# P6_CCD_CAM_BOARD_HDMI.net
KiCad netlist of a schematic drawn in Altium Designer
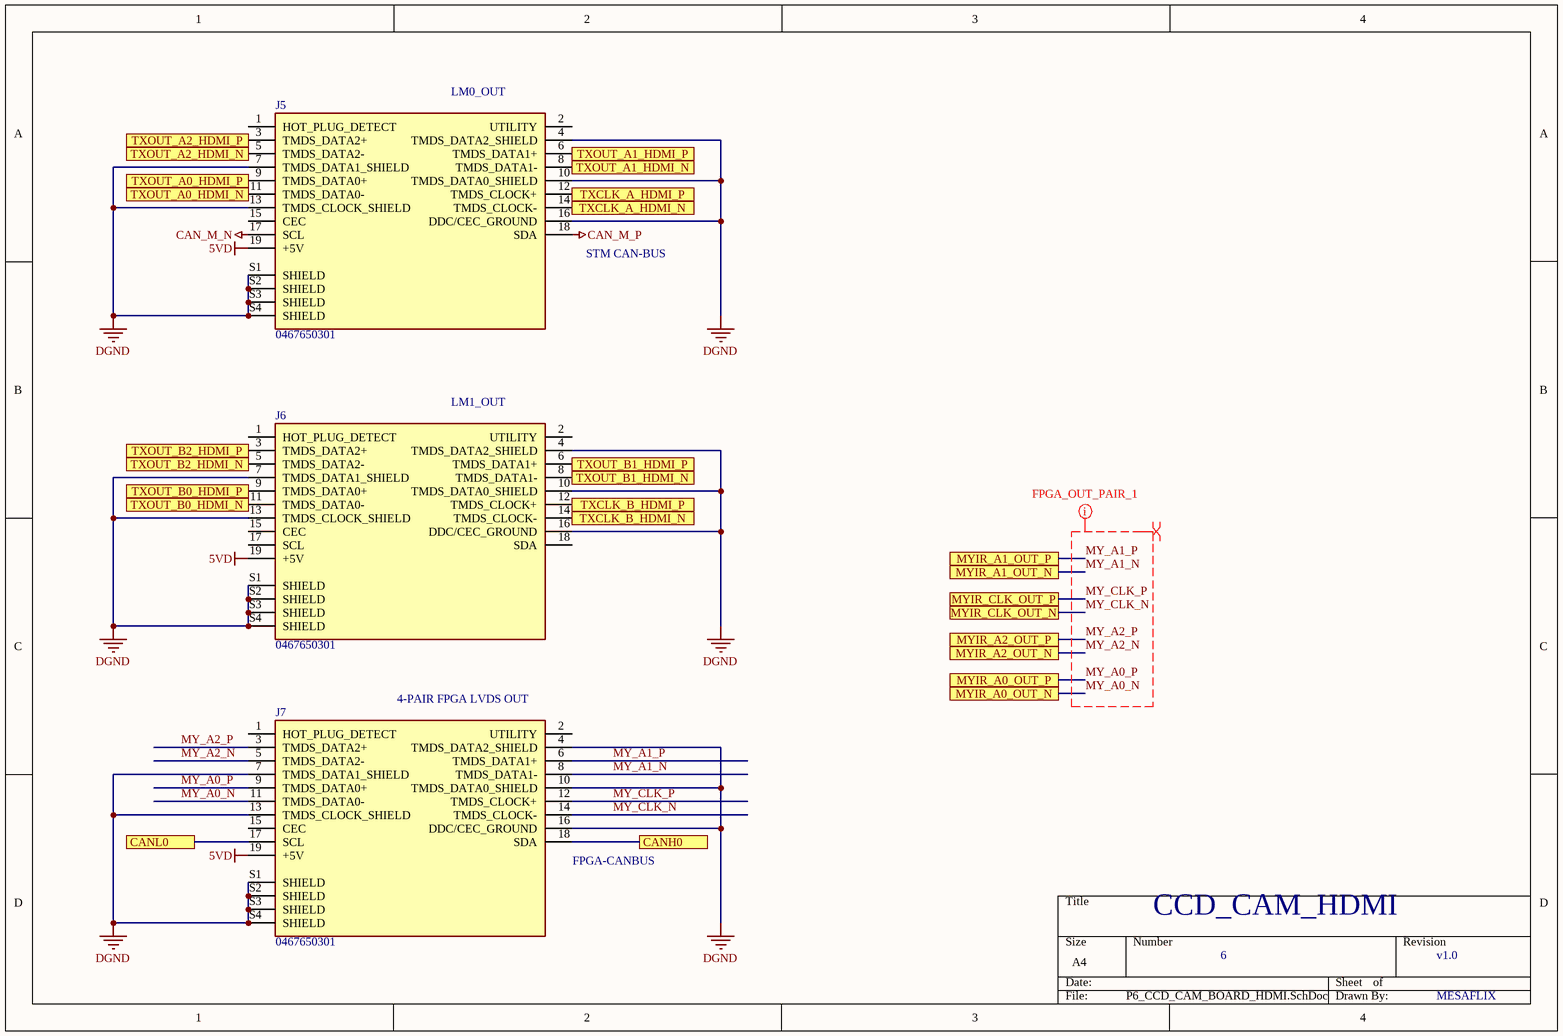
[diagram p0: P6_CCD_CAM_BOARD_HDMI.SchDoc]

(export (version "E")
  (design (tool "Eeschema 10.0.6"))
  (components
    (comp (ref "J5")
      (value "0467650301")
      (footprint "MOLEX_0467650301")
      (description "HDMI - Micro Receptacle Connector 19 Position Surface Mount, Right Angle")
      (fields (field (name "MF") "Molex"))
      (libsource (lib "CCD_CAM_BOARD_1") (part "0467650301"))
    )
    (comp (ref "J6")
      (value "0467650301")
      (footprint "MOLEX_0467650301")
      (description "HDMI - Micro Receptacle Connector 19 Position Surface Mount, Right Angle")
      (fields (field (name "MF") "Molex"))
      (libsource (lib "CCD_CAM_BOARD_1") (part "0467650301"))
    )
    (comp (ref "J7")
      (value "0467650301")
      (footprint "MOLEX_0467650301")
      (description "HDMI - Micro Receptacle Connector 19 Position Surface Mount, Right Angle")
      (fields (field (name "MF") "Molex"))
      (libsource (lib "CCD_CAM_BOARD_1") (part "0467650301"))
    )
  )
  (nets
    (net (code "1") (name "/CANH0") (class "Default")
      (node (ref "J7") (pin "18") (pinfunction "SDA_18") (pintype "passive"))
    )
    (net (code "2") (name "/CANL0") (class "Default")
      (node (ref "J7") (pin "17") (pinfunction "SCL_17") (pintype "passive"))
    )
    (net (code "3") (name "/MY_A0_N") (class "Default")
      (node (ref "J7") (pin "11") (pinfunction "TMDS_DATA0-_11") (pintype "passive"))
    )
    (net (code "4") (name "/MY_A0_P") (class "Default")
      (node (ref "J7") (pin "9") (pinfunction "TMDS_DATA0+_9") (pintype "passive"))
    )
    (net (code "5") (name "/MY_A1_N") (class "Default")
      (node (ref "J7") (pin "8") (pinfunction "TMDS_DATA1-_8") (pintype "passive"))
    )
    (net (code "6") (name "/MY_A1_P") (class "Default")
      (node (ref "J7") (pin "6") (pinfunction "TMDS_DATA1+_6") (pintype "passive"))
    )
    (net (code "7") (name "/MY_A2_N") (class "Default")
      (node (ref "J7") (pin "5") (pinfunction "TMDS_DATA2-_5") (pintype "passive"))
    )
    (net (code "8") (name "/MY_A2_P") (class "Default")
      (node (ref "J7") (pin "3") (pinfunction "TMDS_DATA2+_3") (pintype "passive"))
    )
    (net (code "9") (name "/MY_CLK_N") (class "Default")
      (node (ref "J7") (pin "14") (pinfunction "TMDS_CLOCK-_14") (pintype "passive"))
    )
    (net (code "10") (name "/MY_CLK_P") (class "Default")
      (node (ref "J7") (pin "12") (pinfunction "TMDS_CLOCK+_12") (pintype "passive"))
    )
    (net (code "11") (name "/TXCLK_A_HDMI_N") (class "Default")
      (node (ref "J5") (pin "14") (pinfunction "TMDS_CLOCK-_14") (pintype "passive"))
    )
    (net (code "12") (name "/TXCLK_A_HDMI_P") (class "Default")
      (node (ref "J5") (pin "12") (pinfunction "TMDS_CLOCK+_12") (pintype "passive"))
    )
    (net (code "13") (name "/TXCLK_B_HDMI_N") (class "Default")
      (node (ref "J6") (pin "14") (pinfunction "TMDS_CLOCK-_14") (pintype "passive"))
    )
    (net (code "14") (name "/TXCLK_B_HDMI_P") (class "Default")
      (node (ref "J6") (pin "12") (pinfunction "TMDS_CLOCK+_12") (pintype "passive"))
    )
    (net (code "15") (name "/TXOUT_A0_HDMI_N") (class "Default")
      (node (ref "J5") (pin "11") (pinfunction "TMDS_DATA0-_11") (pintype "passive"))
    )
    (net (code "16") (name "/TXOUT_A0_HDMI_P") (class "Default")
      (node (ref "J5") (pin "9") (pinfunction "TMDS_DATA0+_9") (pintype "passive"))
    )
    (net (code "17") (name "/TXOUT_A1_HDMI_N") (class "Default")
      (node (ref "J5") (pin "8") (pinfunction "TMDS_DATA1-_8") (pintype "passive"))
    )
    (net (code "18") (name "/TXOUT_A1_HDMI_P") (class "Default")
      (node (ref "J5") (pin "6") (pinfunction "TMDS_DATA1+_6") (pintype "passive"))
    )
    (net (code "19") (name "/TXOUT_A2_HDMI_N") (class "Default")
      (node (ref "J5") (pin "5") (pinfunction "TMDS_DATA2-_5") (pintype "passive"))
    )
    (net (code "20") (name "/TXOUT_A2_HDMI_P") (class "Default")
      (node (ref "J5") (pin "3") (pinfunction "TMDS_DATA2+_3") (pintype "passive"))
    )
    (net (code "21") (name "/TXOUT_B0_HDMI_N") (class "Default")
      (node (ref "J6") (pin "11") (pinfunction "TMDS_DATA0-_11") (pintype "passive"))
    )
    (net (code "22") (name "/TXOUT_B0_HDMI_P") (class "Default")
      (node (ref "J6") (pin "9") (pinfunction "TMDS_DATA0+_9") (pintype "passive"))
    )
    (net (code "23") (name "/TXOUT_B1_HDMI_N") (class "Default")
      (node (ref "J6") (pin "8") (pinfunction "TMDS_DATA1-_8") (pintype "passive"))
    )
    (net (code "24") (name "/TXOUT_B1_HDMI_P") (class "Default")
      (node (ref "J6") (pin "6") (pinfunction "TMDS_DATA1+_6") (pintype "passive"))
    )
    (net (code "25") (name "/TXOUT_B2_HDMI_N") (class "Default")
      (node (ref "J6") (pin "5") (pinfunction "TMDS_DATA2-_5") (pintype "passive"))
    )
    (net (code "26") (name "/TXOUT_B2_HDMI_P") (class "Default")
      (node (ref "J6") (pin "3") (pinfunction "TMDS_DATA2+_3") (pintype "passive"))
    )
    (net (code "27") (name "5VD") (class "Default")
      (node (ref "J5") (pin "19") (pinfunction "+5V_19") (pintype "passive"))
      (node (ref "J6") (pin "19") (pinfunction "+5V_19") (pintype "passive"))
      (node (ref "J7") (pin "19") (pinfunction "+5V_19") (pintype "passive"))
    )
    (net (code "28") (name "CAN_M_N") (class "Default")
      (node (ref "J5") (pin "17") (pinfunction "SCL_17") (pintype "passive"))
    )
    (net (code "29") (name "CAN_M_P") (class "Default")
      (node (ref "J5") (pin "18") (pinfunction "SDA_18") (pintype "passive"))
    )
    (net (code "30") (name "DGND") (class "Default")
      (node (ref "J5") (pin "10") (pinfunction "TMDS_DATA0_SHIELD_10") (pintype "passive"))
      (node (ref "J5") (pin "13") (pinfunction "TMDS_CLOCK_SHIELD_13") (pintype "passive"))
      (node (ref "J5") (pin "16") (pinfunction "DDC/CEC_GROUND_16") (pintype "passive"))
      (node (ref "J5") (pin "4") (pinfunction "TMDS_DATA2_SHIELD_4") (pintype "passive"))
      (node (ref "J5") (pin "7") (pinfunction "TMDS_DATA1_SHIELD_7") (pintype "passive"))
      (node (ref "J5") (pin "S1") (pinfunction "SHIELD_S1") (pintype "passive"))
      (node (ref "J5") (pin "S2") (pinfunction "SHIELD_S2") (pintype "passive"))
      (node (ref "J5") (pin "S3") (pinfunction "SHIELD_S3") (pintype "passive"))
      (node (ref "J5") (pin "S4") (pinfunction "SHIELD_S4") (pintype "passive"))
      (node (ref "J6") (pin "10") (pinfunction "TMDS_DATA0_SHIELD_10") (pintype "passive"))
      (node (ref "J6") (pin "13") (pinfunction "TMDS_CLOCK_SHIELD_13") (pintype "passive"))
      (node (ref "J6") (pin "16") (pinfunction "DDC/CEC_GROUND_16") (pintype "passive"))
      (node (ref "J6") (pin "4") (pinfunction "TMDS_DATA2_SHIELD_4") (pintype "passive"))
      (node (ref "J6") (pin "7") (pinfunction "TMDS_DATA1_SHIELD_7") (pintype "passive"))
      (node (ref "J6") (pin "S1") (pinfunction "SHIELD_S1") (pintype "passive"))
      (node (ref "J6") (pin "S2") (pinfunction "SHIELD_S2") (pintype "passive"))
      (node (ref "J6") (pin "S3") (pinfunction "SHIELD_S3") (pintype "passive"))
      (node (ref "J6") (pin "S4") (pinfunction "SHIELD_S4") (pintype "passive"))
      (node (ref "J7") (pin "10") (pinfunction "TMDS_DATA0_SHIELD_10") (pintype "passive"))
      (node (ref "J7") (pin "13") (pinfunction "TMDS_CLOCK_SHIELD_13") (pintype "passive"))
      (node (ref "J7") (pin "16") (pinfunction "DDC/CEC_GROUND_16") (pintype "passive"))
      (node (ref "J7") (pin "4") (pinfunction "TMDS_DATA2_SHIELD_4") (pintype "passive"))
      (node (ref "J7") (pin "7") (pinfunction "TMDS_DATA1_SHIELD_7") (pintype "passive"))
      (node (ref "J7") (pin "S1") (pinfunction "SHIELD_S1") (pintype "passive"))
      (node (ref "J7") (pin "S2") (pinfunction "SHIELD_S2") (pintype "passive"))
      (node (ref "J7") (pin "S3") (pinfunction "SHIELD_S3") (pintype "passive"))
      (node (ref "J7") (pin "S4") (pinfunction "SHIELD_S4") (pintype "passive"))
    )
    (net (code "31") (name "unconnected-(J5-CEC-Pad15)") (class "Default")
      (node (ref "J5") (pin "15") (pinfunction "CEC_15") (pintype "passive"))
    )
    (net (code "32") (name "unconnected-(J5-HOT_PLUG_DETECT-Pad1)") (class "Default")
      (node (ref "J5") (pin "1") (pinfunction "HOT_PLUG_DETECT_1") (pintype "passive"))
    )
    (net (code "33") (name "unconnected-(J5-UTILITY-Pad2)") (class "Default")
      (node (ref "J5") (pin "2") (pinfunction "UTILITY_2") (pintype "passive"))
    )
    (net (code "34") (name "unconnected-(J6-CEC-Pad15)") (class "Default")
      (node (ref "J6") (pin "15") (pinfunction "CEC_15") (pintype "passive"))
    )
    (net (code "35") (name "unconnected-(J6-HOT_PLUG_DETECT-Pad1)") (class "Default")
      (node (ref "J6") (pin "1") (pinfunction "HOT_PLUG_DETECT_1") (pintype "passive"))
    )
    (net (code "36") (name "unconnected-(J6-SCL-Pad17)") (class "Default")
      (node (ref "J6") (pin "17") (pinfunction "SCL_17") (pintype "passive"))
    )
    (net (code "37") (name "unconnected-(J6-SDA-Pad18)") (class "Default")
      (node (ref "J6") (pin "18") (pinfunction "SDA_18") (pintype "passive"))
    )
    (net (code "38") (name "unconnected-(J6-UTILITY-Pad2)") (class "Default")
      (node (ref "J6") (pin "2") (pinfunction "UTILITY_2") (pintype "passive"))
    )
    (net (code "39") (name "unconnected-(J7-CEC-Pad15)") (class "Default")
      (node (ref "J7") (pin "15") (pinfunction "CEC_15") (pintype "passive"))
    )
    (net (code "40") (name "unconnected-(J7-HOT_PLUG_DETECT-Pad1)") (class "Default")
      (node (ref "J7") (pin "1") (pinfunction "HOT_PLUG_DETECT_1") (pintype "passive"))
    )
    (net (code "41") (name "unconnected-(J7-UTILITY-Pad2)") (class "Default")
      (node (ref "J7") (pin "2") (pinfunction "UTILITY_2") (pintype "passive"))
    )
  )
)
